# power.net
KiCad netlist of a schematic drawn in Altium Designer
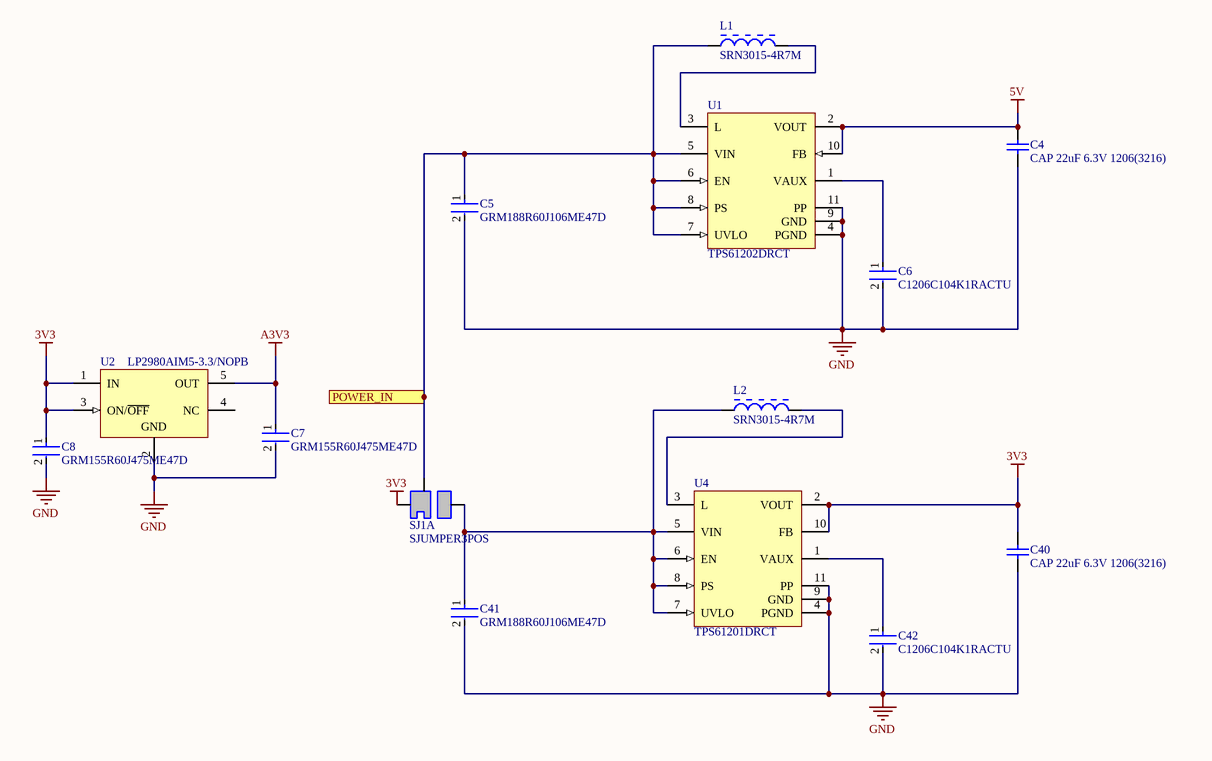
[diagram p0: power.SchDoc]

(export (version "E")
  (design (tool "Eeschema 10.0.6"))
  (components
    (comp (ref "C4")
      (value "CAP 22uF 6.3V 1206(3216)")
      (footprint "CAPC1206(3216)190_M")
      (description "CAP 22uF 6.3V ±20% 1206 (3216 Metric) Thickness 1.9mm SMD")
      (fields (field (name "TOLERANCE") "Â±20%"))
      (libsource (lib "Altium Content Vault") (part "CAP"))
    )
    (comp (ref "C5")
      (value "GRM188R60J106ME47D")
      (footprint "FP-GRM188-0_1-e0_2_0_55-MFG")
      (description "Chip Multilayer Ceramic Capacitors for General Purpose, 0603, 10uF, X5R, 15%, 20%, 6.3V")
      (fields (field (name "VOLTAGE") "6.3V") (field (name "TOLERANCE") "20%"))
      (libsource (lib "Altium Content Vault") (part "02cd4be3c70576c341d710602a673aa"))
    )
    (comp (ref "C6")
      (value "C1206C104K1RACTU")
      (footprint "FP-C1206C-EB-MFG")
      (description "CAP CER 0.1UF 100V X7R 1206")
      (fields
        (field (name "TOLERANCE") "0.1")
        (field (name "OCTOPART") "https://octopart.com/c1206c104k1ractu-kemet-89521")
      )
      (libsource (lib "Altium Content Vault") (part "b4654b650e69147ec39a6b967a45e02"))
    )
    (comp (ref "C7")
      (value "GRM155R60J475ME47D")
      (footprint "FP-GRM155-0_1-IPC_B")
      (description "Chip Multilayer Ceramic Capacitors for General Purpose, 0402, 4.7uF, X5R, 15%, 20%, 6.3V")
      (fields (field (name "VOLTAGE") "6.3V") (field (name "TOLERANCE") "20%"))
      (libsource (lib "Altium Content Vault") (part "11868f565c42a9108669ba33697ecf6"))
    )
    (comp (ref "C8")
      (value "GRM155R60J475ME47D")
      (footprint "FP-GRM155-0_1-IPC_B")
      (description "Chip Multilayer Ceramic Capacitors for General Purpose, 0402, 4.7uF, X5R, 15%, 20%, 6.3V")
      (fields (field (name "VOLTAGE") "6.3V") (field (name "TOLERANCE") "20%"))
      (libsource (lib "Altium Content Vault") (part "11868f565c42a9108669ba33697ecf6"))
    )
    (comp (ref "C40")
      (value "CAP 22uF 6.3V 1206(3216)")
      (footprint "CAPC1206(3216)190_M")
      (description "CAP 22uF 6.3V ±20% 1206 (3216 Metric) Thickness 1.9mm SMD")
      (fields (field (name "TOLERANCE") "Â±20%"))
      (libsource (lib "Altium Content Vault") (part "CAP"))
    )
    (comp (ref "C41")
      (value "GRM188R60J106ME47D")
      (footprint "FP-GRM188-0_1-e0_2_0_55-MFG")
      (description "Chip Multilayer Ceramic Capacitors for General Purpose, 0603, 10uF, X5R, 15%, 20%, 6.3V")
      (fields (field (name "VOLTAGE") "6.3V") (field (name "TOLERANCE") "20%"))
      (libsource (lib "Altium Content Vault") (part "02cd4be3c70576c341d710602a673aa"))
    )
    (comp (ref "C42")
      (value "C1206C104K1RACTU")
      (footprint "FP-C1206C-EB-MFG")
      (description "CAP CER 0.1UF 100V X7R 1206")
      (fields
        (field (name "TOLERANCE") "0.1")
        (field (name "OCTOPART") "https://octopart.com/c1206c104k1ractu-kemet-89521")
      )
      (libsource (lib "Altium Content Vault") (part "b4654b650e69147ec39a6b967a45e02"))
    )
    (comp (ref "L1")
      (value "SRN3015-4R7M")
      (footprint "BOUR-SRN3015-2_V")
      (fields (field (name "MANUFACTURER") "Bourns"))
      (libsource (lib "Altium Content Vault") (part "BOUR-IND-2A"))
    )
    (comp (ref "L2")
      (value "SRN3015-4R7M")
      (footprint "BOUR-SRN3015-2_V")
      (fields (field (name "MANUFACTURER") "Bourns"))
      (libsource (lib "Altium Content Vault") (part "BOUR-IND-2A"))
    )
    (comp (ref "SJ1")
      (value "SJUMPER3POS")
      (footprint "SJUMPER3POS-Footprint-1")
      (description "3 pins solder jumper")
      (libsource (lib "EPFL") (part "SJUMPER3POS-Symbol-1"))
    )
    (comp (ref "U1")
      (value "TPS61202DRCT")
      (footprint "DRC0010J_V")
      (fields (field (name "MANUFACTURER") "Texas Instruments"))
      (libsource (lib "Altium Content Vault") (part "TI-TPS61202DRC10-2400X1650TP"))
    )
    (comp (ref "U2")
      (value "LP2980AIM5-3.3/NOPB")
      (footprint "MF05A_L")
      (description "Micropower 50 mA Ultra Low-Dropout Regulator, 5-pin SOT-23, Pb-Free")
      (fields (field (name "MANUFACTURER") "National Semiconductor"))
      (libsource (lib "Altium Content Vault") (part "PM-REG-LP2981-SOT5"))
    )
    (comp (ref "U4")
      (value "TPS61201DRCT")
      (footprint "DRC0010J_V")
      (fields (field (name "MANUFACTURER") "Texas Instruments"))
      (libsource (lib "Altium Content Vault") (part "TI-TPS61201DRC10-2400X1650TP"))
    )
  )
  (nets
    (net (code "1") (name "/POWER_IN") (class "Default")
      (node (ref "C5") (pin "1") (pinfunction "1_1") (pintype "passive"))
      (node (ref "L1") (pin "1") (pinfunction "1_1") (pintype "passive"))
      (node (ref "SJ1") (pin "2") (pinfunction "2_2") (pintype "passive"))
      (node (ref "U1") (pin "5") (pinfunction "VIN_5") (pintype "power_in"))
      (node (ref "U1") (pin "6") (pinfunction "EN_6") (pintype "input"))
      (node (ref "U1") (pin "7") (pinfunction "UVLO_7") (pintype "input"))
      (node (ref "U1") (pin "8") (pinfunction "PS_8") (pintype "input"))
    )
    (net (code "2") (name "3V3") (class "Default")
      (node (ref "C40") (pin "2") (pinfunction "2_2") (pintype "passive"))
      (node (ref "C8") (pin "1") (pinfunction "1_1") (pintype "passive"))
      (node (ref "SJ1") (pin "1") (pinfunction "1_1") (pintype "passive"))
      (node (ref "U2") (pin "1") (pinfunction "IN_1") (pintype "power_in"))
      (node (ref "U2") (pin "3") (pinfunction "ON/~{OFF}_3") (pintype "input"))
      (node (ref "U4") (pin "10") (pinfunction "FB_10") (pintype "passive"))
      (node (ref "U4") (pin "2") (pinfunction "VOUT_2") (pintype "power_in"))
    )
    (net (code "3") (name "5V") (class "Default")
      (node (ref "C4") (pin "2") (pinfunction "2_2") (pintype "passive"))
      (node (ref "U1") (pin "10") (pinfunction "FB_10") (pintype "input"))
      (node (ref "U1") (pin "2") (pinfunction "VOUT_2") (pintype "power_in"))
    )
    (net (code "4") (name "A3V3") (class "Default")
      (node (ref "C7") (pin "1") (pinfunction "1_1") (pintype "passive"))
      (node (ref "U2") (pin "5") (pinfunction "OUT_5") (pintype "power_in"))
    )
    (net (code "5") (name "GND") (class "Default")
      (node (ref "C4") (pin "1") (pinfunction "1_1") (pintype "passive"))
      (node (ref "C40") (pin "1") (pinfunction "1_1") (pintype "passive"))
      (node (ref "C41") (pin "2") (pinfunction "2_2") (pintype "passive"))
      (node (ref "C42") (pin "2") (pinfunction "2_2") (pintype "passive"))
      (node (ref "C5") (pin "2") (pinfunction "2_2") (pintype "passive"))
      (node (ref "C6") (pin "2") (pinfunction "2_2") (pintype "passive"))
      (node (ref "C7") (pin "2") (pinfunction "2_2") (pintype "passive"))
      (node (ref "C8") (pin "2") (pinfunction "2_2") (pintype "passive"))
      (node (ref "U1") (pin "11") (pinfunction "PP_11") (pintype "power_in"))
      (node (ref "U1") (pin "4") (pinfunction "PGND_4") (pintype "power_in"))
      (node (ref "U1") (pin "9") (pinfunction "GND_9") (pintype "power_in"))
      (node (ref "U2") (pin "2") (pinfunction "GND_2") (pintype "power_in"))
      (node (ref "U4") (pin "11") (pinfunction "PP_11") (pintype "power_in"))
      (node (ref "U4") (pin "4") (pinfunction "PGND_4") (pintype "power_in"))
      (node (ref "U4") (pin "9") (pinfunction "GND_9") (pintype "power_in"))
    )
    (net (code "6") (name "Net-(U1-L)") (class "Default")
      (node (ref "L1") (pin "2") (pinfunction "2_2") (pintype "passive"))
      (node (ref "U1") (pin "3") (pinfunction "L_3") (pintype "power_in"))
    )
    (net (code "7") (name "Net-(U1-VAUX)") (class "Default")
      (node (ref "C6") (pin "1") (pinfunction "1_1") (pintype "passive"))
      (node (ref "U1") (pin "1") (pinfunction "VAUX_1") (pintype "power_in"))
    )
    (net (code "8") (name "Net-(U4-EN)") (class "Default")
      (node (ref "C41") (pin "1") (pinfunction "1_1") (pintype "passive"))
      (node (ref "L2") (pin "1") (pinfunction "1_1") (pintype "passive"))
      (node (ref "SJ1") (pin "3") (pinfunction "3_3") (pintype "passive"))
      (node (ref "U4") (pin "5") (pinfunction "VIN_5") (pintype "power_in"))
      (node (ref "U4") (pin "6") (pinfunction "EN_6") (pintype "input"))
      (node (ref "U4") (pin "7") (pinfunction "UVLO_7") (pintype "input"))
      (node (ref "U4") (pin "8") (pinfunction "PS_8") (pintype "input"))
    )
    (net (code "9") (name "Net-(U4-L)") (class "Default")
      (node (ref "L2") (pin "2") (pinfunction "2_2") (pintype "passive"))
      (node (ref "U4") (pin "3") (pinfunction "L_3") (pintype "power_in"))
    )
    (net (code "10") (name "Net-(U4-VAUX)") (class "Default")
      (node (ref "C42") (pin "1") (pinfunction "1_1") (pintype "passive"))
      (node (ref "U4") (pin "1") (pinfunction "VAUX_1") (pintype "power_in"))
    )
    (net (code "11") (name "unconnected-(U2-NC-Pad4)") (class "Default")
      (node (ref "U2") (pin "4") (pinfunction "NC_4") (pintype "passive"))
    )
  )
)
